# Power_Distribution_Board.net
KiCad netlist of a schematic drawn in EAGLE
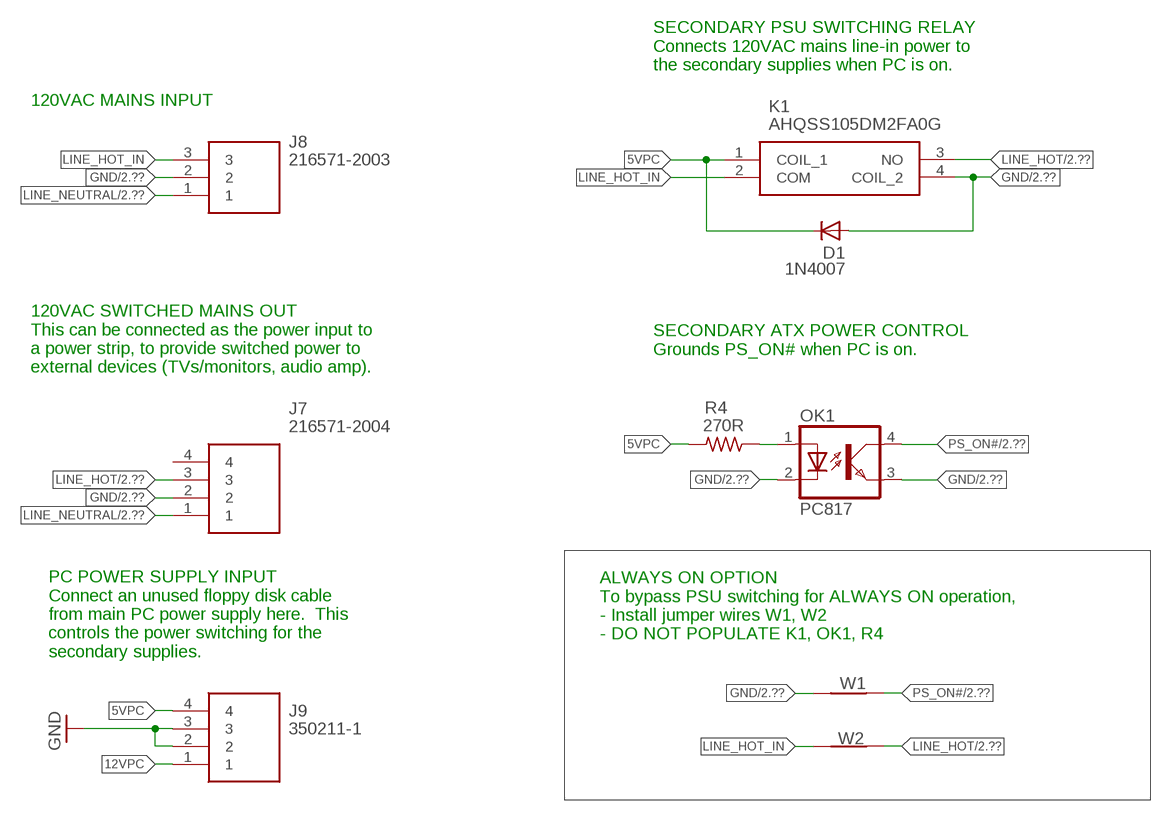
[diagram p0: schematic, sheet 1]
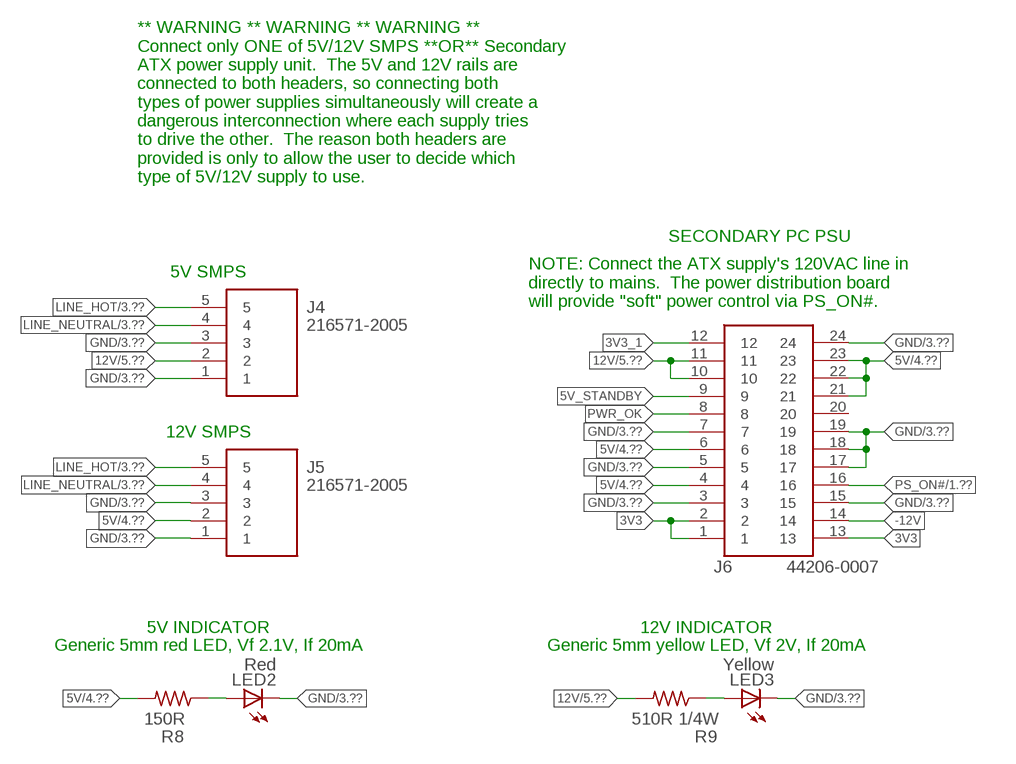
[diagram p1: schematic, sheet 2]
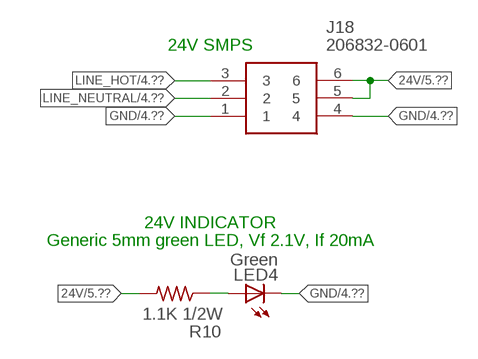
[diagram p2: schematic, sheet 3]
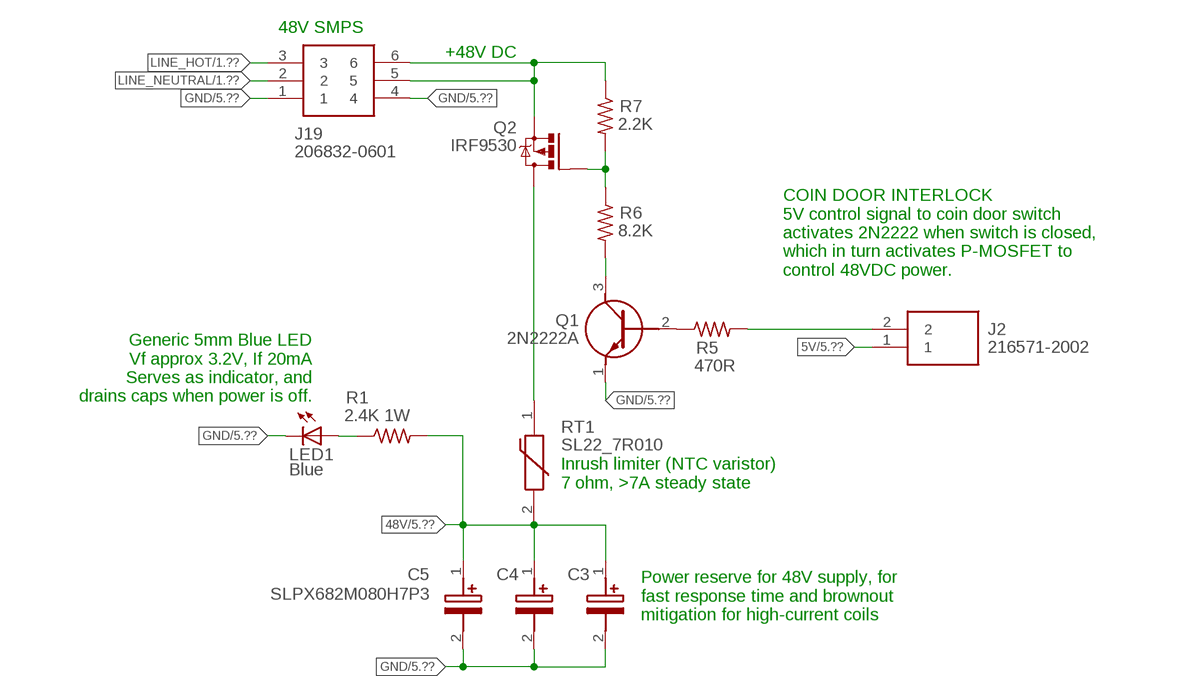
[diagram p3: schematic, sheet 4]
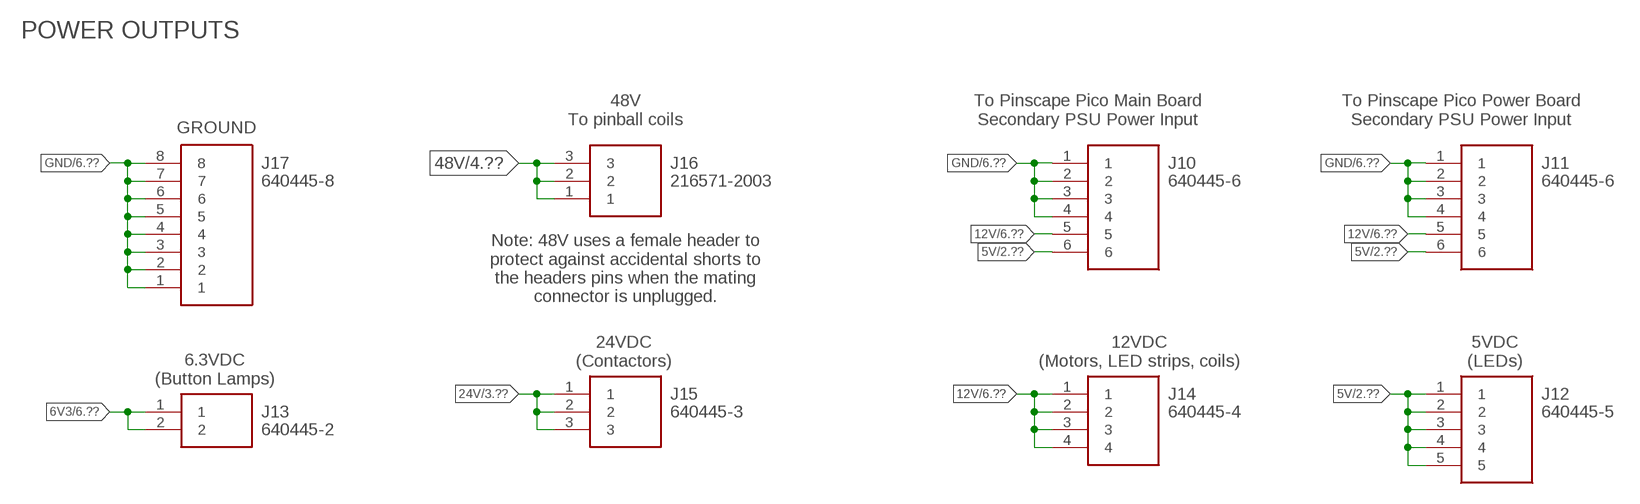
[diagram p4: schematic, sheet 5]
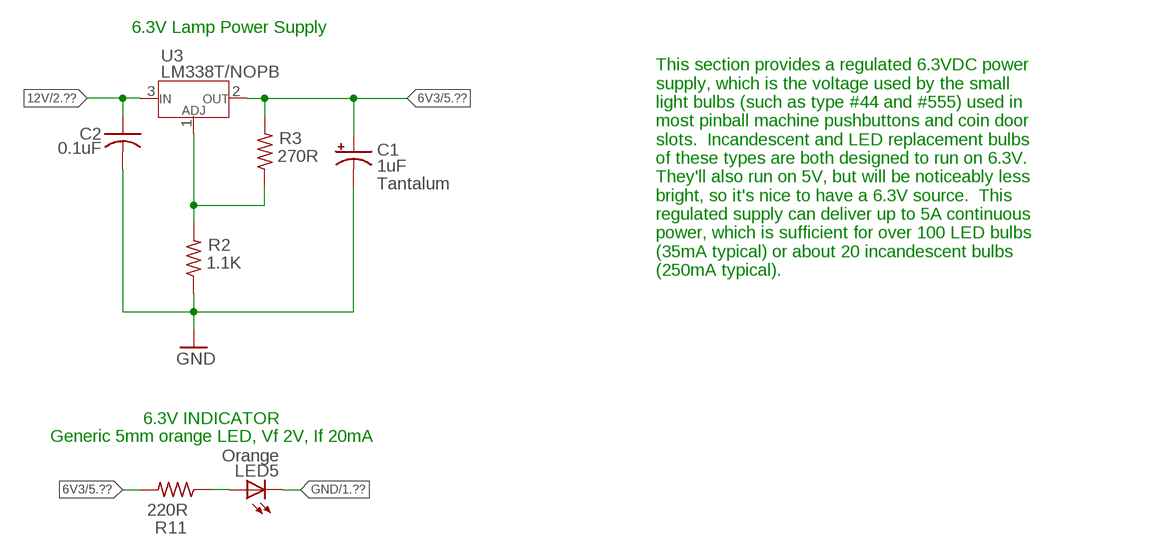
[diagram p5: schematic, sheet 6]

(export (version "E")
  (design (tool "Eeschema 10.0.6"))
  (components
    (comp (ref "C3")
      (value "SLPX682M080H7P3")
      (footprint "eagle-import:CAPPRD1000W100D3550H4200")
      (fields (field (name "MOUSER_PART_NUMBER") "598-SLPX682M080H7P3"))
      (libsource (lib "eagle-import") (part "SLPX682M080H7P3"))
    )
    (comp (ref "C4")
      (value "SLPX682M080H7P3")
      (footprint "eagle-import:CAPPRD1000W100D3550H4200")
      (fields (field (name "MOUSER_PART_NUMBER") "598-SLPX682M080H7P3"))
      (libsource (lib "eagle-import") (part "SLPX682M080H7P3"))
    )
    (comp (ref "C5")
      (value "SLPX682M080H7P3")
      (footprint "eagle-import:CAPPRD1000W100D3550H4200")
      (fields (field (name "MOUSER_PART_NUMBER") "598-SLPX682M080H7P3"))
      (libsource (lib "eagle-import") (part "SLPX682M080H7P3"))
    )
    (comp (ref "J2")
      (value "216571-2002")
      (footprint "eagle-import:216571-YY02_1")
      (fields (field (name "MOUSER_PART_NUMBER") "538-216571-2002"))
      (libsource (lib "eagle-import") (part "216571-2002"))
    )
    (comp (ref "J19")
      (value "206832-0601")
      (footprint "eagle-import:2068320601")
      (fields (field (name "MOUSER_PART_NUMBER") "538-206832-0601"))
      (libsource (lib "eagle-import") (part "206832-0601"))
    )
    (comp (ref "LED1")
      (value "Blue")
      (footprint "eagle-import:LED5MM")
      (libsource (lib "eagle-import") (part "LED5MM"))
    )
    (comp (ref "Q1")
      (value "2N2222A")
      (footprint "eagle-import:2N2222A")
      (fields (field (name "MOUSER_PART_NUMBER") "637-2N2222A"))
      (libsource (lib "eagle-import") (part "2N2222A"))
    )
    (comp (ref "Q2")
      (value "IRF9530")
      (footprint "eagle-import:TO220BV")
      (libsource (lib "eagle-import") (part "IRF9530"))
    )
    (comp (ref "R1")
      (value "2.4K 1W")
      (footprint "eagle-import:0309_12")
      (libsource (lib "eagle-import") (part "R-US_0309/12"))
    )
    (comp (ref "R5")
      (value "470R")
      (footprint "eagle-import:0204_7")
      (libsource (lib "eagle-import") (part "R-US_0204/7"))
    )
    (comp (ref "R6")
      (value "8.2K")
      (footprint "eagle-import:0207_10")
      (libsource (lib "eagle-import") (part "R-US_0207/10"))
    )
    (comp (ref "R7")
      (value "2.2K")
      (footprint "eagle-import:0207_10")
      (libsource (lib "eagle-import") (part "R-US_0207/10"))
    )
    (comp (ref "RT1")
      (value "SL22_7R010")
      (footprint "eagle-import:SL227R010")
      (fields
        (field (name "MANUFACTURER_PART_NUMBER") "SL22 7R010")
        (field (name "MOUSER_PART_NUMBER") "995-SL22-7R010")
      )
      (libsource (lib "eagle-import") (part "SL22_7R010"))
    )
    (comp (ref "J10")
      (value "640445-6")
      (footprint "eagle-import:SHDR6W183P0X396_1X6_2377X762X1")
      (fields (field (name "MOUSER_PART_NUMBER") "571-6404456"))
      (libsource (lib "eagle-import") (part "640445-6"))
    )
    (comp (ref "J11")
      (value "640445-6")
      (footprint "eagle-import:SHDR6W183P0X396_1X6_2377X762X1")
      (fields (field (name "MOUSER_PART_NUMBER") "571-6404456"))
      (libsource (lib "eagle-import") (part "640445-6"))
    )
    (comp (ref "J12")
      (value "640445-5")
      (footprint "eagle-import:HDRV5W117P0X396_1X5_1981X762X1")
      (fields (field (name "MOUSER_PART_NUMBER") "571-640445-5"))
      (libsource (lib "eagle-import") (part "640445-5"))
    )
    (comp (ref "J13")
      (value "640445-2")
      (footprint "eagle-import:SHDR2W117P0X396_1X2_792X762X11")
      (fields (field (name "MOUSER_PART_NUMBER") "5716404452"))
      (libsource (lib "eagle-import") (part "640445-2"))
    )
    (comp (ref "J14")
      (value "640445-4")
      (footprint "eagle-import:SHDR4W117P0X396_1X4_1585X762X1")
      (fields (field (name "MOUSER_PART_NUMBER") "571-6404454"))
      (libsource (lib "eagle-import") (part "640445-4"))
    )
    (comp (ref "J15")
      (value "640445-3")
      (footprint "eagle-import:HDRV3W140P0X396_1X3_1189X762X1")
      (fields (field (name "MOUSER_PART_NUMBER") "571-6404453"))
      (libsource (lib "eagle-import") (part "640445-3"))
    )
    (comp (ref "J16")
      (value "216571-2003")
      (footprint "eagle-import:216571-YY03_1")
      (fields (field (name "MOUSER_PART_NUMBER") "538-216571-2003"))
      (libsource (lib "eagle-import") (part "216571-2003"))
    )
    (comp (ref "J17")
      (value "640445-8")
      (footprint "eagle-import:SHDR8W117P0X396_1X8_3170X762X1")
      (fields (field (name "MOUSER_PART_NUMBER") "571-6404458"))
      (libsource (lib "eagle-import") (part "640445-8"))
    )
    (comp (ref "D1")
      (value "1N4007")
      (footprint "eagle-import:DO41-10")
      (libsource (lib "eagle-import") (part "1N4007"))
    )
    (comp (ref "J7")
      (value "216571-2004")
      (footprint "eagle-import:216571-YY04_1")
      (fields (field (name "MOUSER_PART_NUMBER") "538-216571-2004"))
      (libsource (lib "eagle-import") (part "216571-2004"))
    )
    (comp (ref "J8")
      (value "216571-2003")
      (footprint "eagle-import:216571-YY03_1")
      (fields (field (name "MOUSER_PART_NUMBER") "538-216571-2003"))
      (libsource (lib "eagle-import") (part "216571-2003"))
    )
    (comp (ref "J9")
      (value "350211-1")
      (footprint "eagle-import:3502111")
      (fields (field (name "MOUSER_PART_NUMBER") "571-3502111"))
      (libsource (lib "eagle-import") (part "350211-1"))
    )
    (comp (ref "K1")
      (value "AHQSS105DM2FA0G")
      (footprint "eagle-import:AHQSS105DM2FA0G")
      (fields (field (name "MOUSER_PART_NUMBER") "523-AHQSS105DM2FA0G"))
      (libsource (lib "eagle-import") (part "AHQSS105DM2FA0G"))
    )
    (comp (ref "OK1")
      (value "PC817")
      (footprint "eagle-import:DIL04")
      (fields (field (name "MPN") "PC817X4J000F"))
      (libsource (lib "eagle-import") (part "PC817"))
    )
    (comp (ref "R4")
      (value "270R")
      (footprint "eagle-import:0204_7")
      (libsource (lib "eagle-import") (part "R-US_0204/7"))
    )
    (comp (ref "W1")
      (value "JUMPER-WIRE")
      (footprint "eagle-import:JUMPER-WIRE")
      (libsource (lib "eagle-import") (part "JUMPER-WIRE"))
    )
    (comp (ref "W2")
      (value "JUMPER-WIRE")
      (footprint "eagle-import:JUMPER-WIRE")
      (libsource (lib "eagle-import") (part "JUMPER-WIRE"))
    )
    (comp (ref "J18")
      (value "206832-0601")
      (footprint "eagle-import:2068320601")
      (fields (field (name "MOUSER_PART_NUMBER") "538-206832-0601"))
      (libsource (lib "eagle-import") (part "206832-0601"))
    )
    (comp (ref "LED4")
      (value "Green")
      (footprint "eagle-import:LED5MM")
      (libsource (lib "eagle-import") (part "LED5MM"))
    )
    (comp (ref "R10")
      (value "1.1K 1/2W")
      (footprint "eagle-import:0309_12")
      (libsource (lib "eagle-import") (part "R-US_0309/12"))
    )
    (comp (ref "J4")
      (value "216571-2005")
      (footprint "eagle-import:216571-YY05_1")
      (fields (field (name "MOUSER_PART_NUMBER") "538-216571-2005"))
      (libsource (lib "eagle-import") (part "216571-2005"))
    )
    (comp (ref "J5")
      (value "216571-2005")
      (footprint "eagle-import:216571-YY05_1")
      (fields (field (name "MOUSER_PART_NUMBER") "538-216571-2005"))
      (libsource (lib "eagle-import") (part "216571-2005"))
    )
    (comp (ref "J6")
      (value "44206-0007")
      (footprint "eagle-import:44206-0007_1")
      (fields (field (name "MOUSER_PART_NUMBER") "538-44206-0007"))
      (libsource (lib "eagle-import") (part "44206-0007"))
    )
    (comp (ref "LED2")
      (value "Red")
      (footprint "eagle-import:LED5MM")
      (libsource (lib "eagle-import") (part "LED5MM"))
    )
    (comp (ref "LED3")
      (value "Yellow")
      (footprint "eagle-import:LED5MM")
      (libsource (lib "eagle-import") (part "LED5MM"))
    )
    (comp (ref "R8")
      (value "150R")
      (footprint "eagle-import:0309_12")
      (libsource (lib "eagle-import") (part "R-US_0309/12"))
    )
    (comp (ref "R9")
      (value "510R 1/4W")
      (footprint "eagle-import:0309_12")
      (libsource (lib "eagle-import") (part "R-US_0309/12"))
    )
    (comp (ref "C1")
      (value "1uF")
      (footprint "eagle-import:B45181B")
      (libsource (lib "eagle-import") (part "CPOL-US_TANTALUMB45181B"))
    )
    (comp (ref "C2")
      (value "0.1uF")
      (footprint "eagle-import:C025-030X050")
      (libsource (lib "eagle-import") (part "C-US025-030X050"))
    )
    (comp (ref "LED5")
      (value "Orange")
      (footprint "eagle-import:LED5MM")
      (libsource (lib "eagle-import") (part "LED5MM"))
    )
    (comp (ref "R2")
      (value "1.1K")
      (footprint "eagle-import:0204_7")
      (libsource (lib "eagle-import") (part "R-US_0204/7"))
    )
    (comp (ref "R3")
      (value "270R")
      (footprint "eagle-import:0204_7")
      (libsource (lib "eagle-import") (part "R-US_0204/7"))
    )
    (comp (ref "R11")
      (value "220R")
      (footprint "eagle-import:0309_12")
      (libsource (lib "eagle-import") (part "R-US_0309/12"))
    )
    (comp (ref "U3")
      (value "LM338T/NOPB")
      (footprint "eagle-import:T03B_TEX")
      (fields (field (name "COPYRIGHT") "Copyright (C) 2023 Ultra Librarian. All rights reserved."))
      (libsource (lib "eagle-import") (part "LM338T/NOPB"))
    )
  )
  (nets
    (net (code "1") (name "-12V") (class "Default")
      (node (ref "J6") (pin "14") (pinfunction "14_14") (pintype "bidirectional"))
    )
    (net (code "2") (name "3V3") (class "Default")
      (node (ref "J6") (pin "1") (pinfunction "1_1") (pintype "bidirectional"))
      (node (ref "J6") (pin "13") (pinfunction "13_13") (pintype "bidirectional"))
      (node (ref "J6") (pin "2") (pinfunction "2_2") (pintype "bidirectional"))
    )
    (net (code "3") (name "3V3_1") (class "Default")
      (node (ref "J6") (pin "12") (pinfunction "12_12") (pintype "bidirectional"))
    )
    (net (code "4") (name "5V") (class "Default")
      (node (ref "J10") (pin "6") (pinfunction "6_6") (pintype "bidirectional"))
      (node (ref "J11") (pin "6") (pinfunction "6_6") (pintype "bidirectional"))
      (node (ref "J12") (pin "1") (pinfunction "1_1") (pintype "bidirectional"))
      (node (ref "J12") (pin "2") (pinfunction "2_2") (pintype "bidirectional"))
      (node (ref "J12") (pin "3") (pinfunction "3_3") (pintype "bidirectional"))
      (node (ref "J12") (pin "4") (pinfunction "4_4") (pintype "bidirectional"))
      (node (ref "J12") (pin "5") (pinfunction "5_5") (pintype "bidirectional"))
      (node (ref "J2") (pin "1") (pinfunction "1_1") (pintype "bidirectional"))
      (node (ref "J5") (pin "2") (pinfunction "2_2") (pintype "bidirectional"))
      (node (ref "J6") (pin "21") (pinfunction "21_21") (pintype "bidirectional"))
      (node (ref "J6") (pin "22") (pinfunction "22_22") (pintype "bidirectional"))
      (node (ref "J6") (pin "23") (pinfunction "23_23") (pintype "bidirectional"))
      (node (ref "J6") (pin "4") (pinfunction "4_4") (pintype "bidirectional"))
      (node (ref "J6") (pin "6") (pinfunction "6_6") (pintype "bidirectional"))
      (node (ref "R8") (pin "2") (pinfunction "2_2") (pintype "passive"))
    )
    (net (code "5") (name "5VPC") (class "Default")
      (node (ref "D1") (pin "C") (pinfunction "C_C") (pintype "passive"))
      (node (ref "J9") (pin "4") (pinfunction "4_4") (pintype "bidirectional"))
      (node (ref "K1") (pin "1") (pinfunction "COIL_1_1") (pintype "bidirectional"))
      (node (ref "R4") (pin "2") (pinfunction "2_2") (pintype "passive"))
    )
    (net (code "6") (name "5V_STANDBY") (class "Default")
      (node (ref "J6") (pin "9") (pinfunction "9_9") (pintype "bidirectional"))
    )
    (net (code "7") (name "6V3") (class "Default")
      (node (ref "C1") (pin "+") (pinfunction "+_+") (pintype "passive"))
      (node (ref "J13") (pin "1") (pinfunction "1_1") (pintype "bidirectional"))
      (node (ref "J13") (pin "2") (pinfunction "2_2") (pintype "bidirectional"))
      (node (ref "R11") (pin "2") (pinfunction "2_2") (pintype "passive"))
      (node (ref "R3") (pin "2") (pinfunction "2_2") (pintype "passive"))
      (node (ref "U3") (pin "2") (pinfunction "OUT_2") (pintype "power_in"))
    )
    (net (code "8") (name "12V") (class "Default")
      (node (ref "C2") (pin "1") (pinfunction "1_1") (pintype "passive"))
      (node (ref "J10") (pin "5") (pinfunction "5_5") (pintype "bidirectional"))
      (node (ref "J11") (pin "5") (pinfunction "5_5") (pintype "bidirectional"))
      (node (ref "J14") (pin "1") (pinfunction "1_1") (pintype "bidirectional"))
      (node (ref "J14") (pin "2") (pinfunction "2_2") (pintype "bidirectional"))
      (node (ref "J14") (pin "3") (pinfunction "3_3") (pintype "bidirectional"))
      (node (ref "J14") (pin "4") (pinfunction "4_4") (pintype "bidirectional"))
      (node (ref "J4") (pin "2") (pinfunction "2_2") (pintype "bidirectional"))
      (node (ref "J6") (pin "10") (pinfunction "10_10") (pintype "bidirectional"))
      (node (ref "J6") (pin "11") (pinfunction "11_11") (pintype "bidirectional"))
      (node (ref "R9") (pin "2") (pinfunction "2_2") (pintype "passive"))
      (node (ref "U3") (pin "3") (pinfunction "IN_3") (pintype "power_in"))
    )
    (net (code "9") (name "12VPC") (class "Default")
      (node (ref "J9") (pin "1") (pinfunction "1_1") (pintype "bidirectional"))
    )
    (net (code "10") (name "24V") (class "Default")
      (node (ref "J15") (pin "1") (pinfunction "1_1") (pintype "bidirectional"))
      (node (ref "J15") (pin "2") (pinfunction "2_2") (pintype "bidirectional"))
      (node (ref "J15") (pin "3") (pinfunction "3_3") (pintype "bidirectional"))
      (node (ref "J18") (pin "5") (pinfunction "5_5") (pintype "bidirectional"))
      (node (ref "J18") (pin "6") (pinfunction "6_6") (pintype "bidirectional"))
      (node (ref "R10") (pin "2") (pinfunction "2_2") (pintype "passive"))
    )
    (net (code "11") (name "48V") (class "Default")
      (node (ref "C3") (pin "1") (pinfunction "+_1") (pintype "bidirectional"))
      (node (ref "C4") (pin "1") (pinfunction "+_1") (pintype "bidirectional"))
      (node (ref "C5") (pin "1") (pinfunction "+_1") (pintype "bidirectional"))
      (node (ref "J16") (pin "1") (pinfunction "1_1") (pintype "bidirectional"))
      (node (ref "J16") (pin "2") (pinfunction "2_2") (pintype "bidirectional"))
      (node (ref "J16") (pin "3") (pinfunction "3_3") (pintype "bidirectional"))
      (node (ref "R1") (pin "2") (pinfunction "2_2") (pintype "passive"))
      (node (ref "RT1") (pin "2") (pinfunction "2_2") (pintype "bidirectional"))
    )
    (net (code "12") (name "GND") (class "Default")
      (node (ref "C1") (pin "-") (pinfunction "-_-") (pintype "passive"))
      (node (ref "C2") (pin "2") (pinfunction "2_2") (pintype "passive"))
      (node (ref "C3") (pin "2") (pinfunction "-_2") (pintype "bidirectional"))
      (node (ref "C4") (pin "2") (pinfunction "-_2") (pintype "bidirectional"))
      (node (ref "C5") (pin "2") (pinfunction "-_2") (pintype "bidirectional"))
      (node (ref "D1") (pin "A") (pinfunction "A_A") (pintype "passive"))
      (node (ref "J10") (pin "1") (pinfunction "1_1") (pintype "bidirectional"))
      (node (ref "J10") (pin "2") (pinfunction "2_2") (pintype "bidirectional"))
      (node (ref "J10") (pin "3") (pinfunction "3_3") (pintype "bidirectional"))
      (node (ref "J10") (pin "4") (pinfunction "4_4") (pintype "bidirectional"))
      (node (ref "J11") (pin "1") (pinfunction "1_1") (pintype "bidirectional"))
      (node (ref "J11") (pin "2") (pinfunction "2_2") (pintype "bidirectional"))
      (node (ref "J11") (pin "3") (pinfunction "3_3") (pintype "bidirectional"))
      (node (ref "J11") (pin "4") (pinfunction "4_4") (pintype "bidirectional"))
      (node (ref "J17") (pin "1") (pinfunction "1_1") (pintype "bidirectional"))
      (node (ref "J17") (pin "2") (pinfunction "2_2") (pintype "bidirectional"))
      (node (ref "J17") (pin "3") (pinfunction "3_3") (pintype "bidirectional"))
      (node (ref "J17") (pin "4") (pinfunction "4_4") (pintype "bidirectional"))
      (node (ref "J17") (pin "5") (pinfunction "5_5") (pintype "bidirectional"))
      (node (ref "J17") (pin "6") (pinfunction "6_6") (pintype "bidirectional"))
      (node (ref "J17") (pin "7") (pinfunction "7_7") (pintype "bidirectional"))
      (node (ref "J17") (pin "8") (pinfunction "8_8") (pintype "bidirectional"))
      (node (ref "J18") (pin "1") (pinfunction "1_1") (pintype "bidirectional"))
      (node (ref "J18") (pin "4") (pinfunction "4_4") (pintype "bidirectional"))
      (node (ref "J19") (pin "1") (pinfunction "1_1") (pintype "bidirectional"))
      (node (ref "J19") (pin "4") (pinfunction "4_4") (pintype "bidirectional"))
      (node (ref "J4") (pin "1") (pinfunction "1_1") (pintype "bidirectional"))
      (node (ref "J4") (pin "3") (pinfunction "3_3") (pintype "bidirectional"))
      (node (ref "J5") (pin "1") (pinfunction "1_1") (pintype "bidirectional"))
      (node (ref "J5") (pin "3") (pinfunction "3_3") (pintype "bidirectional"))
      (node (ref "J6") (pin "15") (pinfunction "15_15") (pintype "bidirectional"))
      (node (ref "J6") (pin "17") (pinfunction "17_17") (pintype "bidirectional"))
      (node (ref "J6") (pin "18") (pinfunction "18_18") (pintype "bidirectional"))
      (node (ref "J6") (pin "19") (pinfunction "19_19") (pintype "bidirectional"))
      (node (ref "J6") (pin "24") (pinfunction "24_24") (pintype "bidirectional"))
      (node (ref "J6") (pin "3") (pinfunction "3_3") (pintype "bidirectional"))
      (node (ref "J6") (pin "5") (pinfunction "5_5") (pintype "bidirectional"))
      (node (ref "J6") (pin "7") (pinfunction "7_7") (pintype "bidirectional"))
      (node (ref "J7") (pin "2") (pinfunction "2_2") (pintype "bidirectional"))
      (node (ref "J8") (pin "2") (pinfunction "2_2") (pintype "bidirectional"))
      (node (ref "J9") (pin "2") (pinfunction "2_2") (pintype "bidirectional"))
      (node (ref "J9") (pin "3") (pinfunction "3_3") (pintype "bidirectional"))
      (node (ref "K1") (pin "4") (pinfunction "COIL_2_4") (pintype "bidirectional"))
      (node (ref "LED1") (pin "K") (pinfunction "C_K") (pintype "passive"))
      (node (ref "LED2") (pin "K") (pinfunction "C_K") (pintype "passive"))
      (node (ref "LED3") (pin "K") (pinfunction "C_K") (pintype "passive"))
      (node (ref "LED4") (pin "K") (pinfunction "C_K") (pintype "passive"))
      (node (ref "LED5") (pin "K") (pinfunction "C_K") (pintype "passive"))
      (node (ref "OK1") (pin "2") (pinfunction "C_2") (pintype "passive"))
      (node (ref "OK1") (pin "3") (pinfunction "EMIT_3") (pintype "passive"))
      (node (ref "Q1") (pin "1") (pinfunction "E_1") (pintype "bidirectional"))
      (node (ref "R2") (pin "1") (pinfunction "1_1") (pintype "passive"))
      (node (ref "W1") (pin "P$1") (pinfunction "P$1_P$1") (pintype "bidirectional"))
    )
    (net (code "13") (name "LINE_HOT") (class "Default")
      (node (ref "J18") (pin "3") (pinfunction "3_3") (pintype "bidirectional"))
      (node (ref "J19") (pin "3") (pinfunction "3_3") (pintype "bidirectional"))
      (node (ref "J4") (pin "5") (pinfunction "5_5") (pintype "bidirectional"))
      (node (ref "J5") (pin "5") (pinfunction "5_5") (pintype "bidirectional"))
      (node (ref "J7") (pin "3") (pinfunction "3_3") (pintype "bidirectional"))
      (node (ref "K1") (pin "3") (pinfunction "NO_3") (pintype "bidirectional"))
      (node (ref "W2") (pin "P$2") (pinfunction "P$2_P$2") (pintype "bidirectional"))
    )
    (net (code "14") (name "LINE_HOT_IN") (class "Default")
      (node (ref "J8") (pin "3") (pinfunction "3_3") (pintype "bidirectional"))
      (node (ref "K1") (pin "2") (pinfunction "COM_2") (pintype "bidirectional"))
      (node (ref "W2") (pin "P$1") (pinfunction "P$1_P$1") (pintype "bidirectional"))
    )
    (net (code "15") (name "LINE_NEUTRAL") (class "Default")
      (node (ref "J18") (pin "2") (pinfunction "2_2") (pintype "bidirectional"))
      (node (ref "J19") (pin "2") (pinfunction "2_2") (pintype "bidirectional"))
      (node (ref "J4") (pin "4") (pinfunction "4_4") (pintype "bidirectional"))
      (node (ref "J5") (pin "4") (pinfunction "4_4") (pintype "bidirectional"))
      (node (ref "J7") (pin "1") (pinfunction "1_1") (pintype "bidirectional"))
      (node (ref "J8") (pin "1") (pinfunction "1_1") (pintype "bidirectional"))
    )
    (net (code "16") (name "Net-(J2-Pad2)") (class "Default")
      (node (ref "J2") (pin "2") (pinfunction "2_2") (pintype "bidirectional"))
      (node (ref "R5") (pin "2") (pinfunction "2_2") (pintype "passive"))
    )
    (net (code "17") (name "Net-(J19-Pad5)") (class "Default")
      (node (ref "J19") (pin "5") (pinfunction "5_5") (pintype "bidirectional"))
      (node (ref "J19") (pin "6") (pinfunction "6_6") (pintype "bidirectional"))
      (node (ref "Q2") (pin "S") (pinfunction "S_S") (pintype "passive"))
      (node (ref "R7") (pin "1") (pinfunction "1_1") (pintype "passive"))
    )
    (net (code "18") (name "Net-(LED1-PadA)") (class "Default")
      (node (ref "LED1") (pin "A") (pinfunction "A_A") (pintype "passive"))
      (node (ref "R1") (pin "1") (pinfunction "1_1") (pintype "passive"))
    )
    (net (code "19") (name "Net-(LED2-PadA)") (class "Default")
      (node (ref "LED2") (pin "A") (pinfunction "A_A") (pintype "passive"))
      (node (ref "R8") (pin "1") (pinfunction "1_1") (pintype "passive"))
    )
    (net (code "20") (name "Net-(LED3-PadA)") (class "Default")
      (node (ref "LED3") (pin "A") (pinfunction "A_A") (pintype "passive"))
      (node (ref "R9") (pin "1") (pinfunction "1_1") (pintype "passive"))
    )
    (net (code "21") (name "Net-(LED4-PadA)") (class "Default")
      (node (ref "LED4") (pin "A") (pinfunction "A_A") (pintype "passive"))
      (node (ref "R10") (pin "1") (pinfunction "1_1") (pintype "passive"))
    )
    (net (code "22") (name "Net-(LED5-PadA)") (class "Default")
      (node (ref "LED5") (pin "A") (pinfunction "A_A") (pintype "passive"))
      (node (ref "R11") (pin "1") (pinfunction "1_1") (pintype "passive"))
    )
    (net (code "23") (name "Net-(OK1-A)") (class "Default")
      (node (ref "OK1") (pin "1") (pinfunction "A_1") (pintype "passive"))
      (node (ref "R4") (pin "1") (pinfunction "1_1") (pintype "passive"))
    )
    (net (code "24") (name "Net-(Q1-B)") (class "Default")
      (node (ref "Q1") (pin "2") (pinfunction "B_2") (pintype "bidirectional"))
      (node (ref "R5") (pin "1") (pinfunction "1_1") (pintype "passive"))
    )
    (net (code "25") (name "Net-(Q1-C)") (class "Default")
      (node (ref "Q1") (pin "3") (pinfunction "C_3") (pintype "bidirectional"))
      (node (ref "R6") (pin "2") (pinfunction "2_2") (pintype "passive"))
    )
    (net (code "26") (name "Net-(Q2-PadD)") (class "Default")
      (node (ref "Q2") (pin "D") (pinfunction "D_D") (pintype "passive"))
      (node (ref "RT1") (pin "1") (pinfunction "1_1") (pintype "bidirectional"))
    )
    (net (code "27") (name "Net-(Q2-PadG)") (class "Default")
      (node (ref "Q2") (pin "G") (pinfunction "G_G") (pintype "passive"))
      (node (ref "R6") (pin "1") (pinfunction "1_1") (pintype "passive"))
      (node (ref "R7") (pin "2") (pinfunction "2_2") (pintype "passive"))
    )
    (net (code "28") (name "Net-(U3-ADJ)") (class "Default")
      (node (ref "R2") (pin "2") (pinfunction "2_2") (pintype "passive"))
      (node (ref "R3") (pin "1") (pinfunction "1_1") (pintype "passive"))
      (node (ref "U3") (pin "1") (pinfunction "ADJ_1") (pintype "input"))
    )
    (net (code "29") (name "PS_ON#") (class "Default")
      (node (ref "J6") (pin "16") (pinfunction "16_16") (pintype "bidirectional"))
      (node (ref "OK1") (pin "4") (pinfunction "COL_4") (pintype "passive"))
      (node (ref "W1") (pin "P$2") (pinfunction "P$2_P$2") (pintype "bidirectional"))
    )
    (net (code "30") (name "PWR_OK") (class "Default")
      (node (ref "J6") (pin "8") (pinfunction "8_8") (pintype "bidirectional"))
    )
    (net (code "31") (name "unconnected-(J6-Pad20)") (class "Default")
      (node (ref "J6") (pin "20") (pinfunction "20_20") (pintype "bidirectional"))
    )
    (net (code "32") (name "unconnected-(J7-Pad4)") (class "Default")
      (node (ref "J7") (pin "4") (pinfunction "4_4") (pintype "bidirectional"))
    )
  )
)
